# R111F.net
KiCad netlist of a schematic drawn in EAGLE
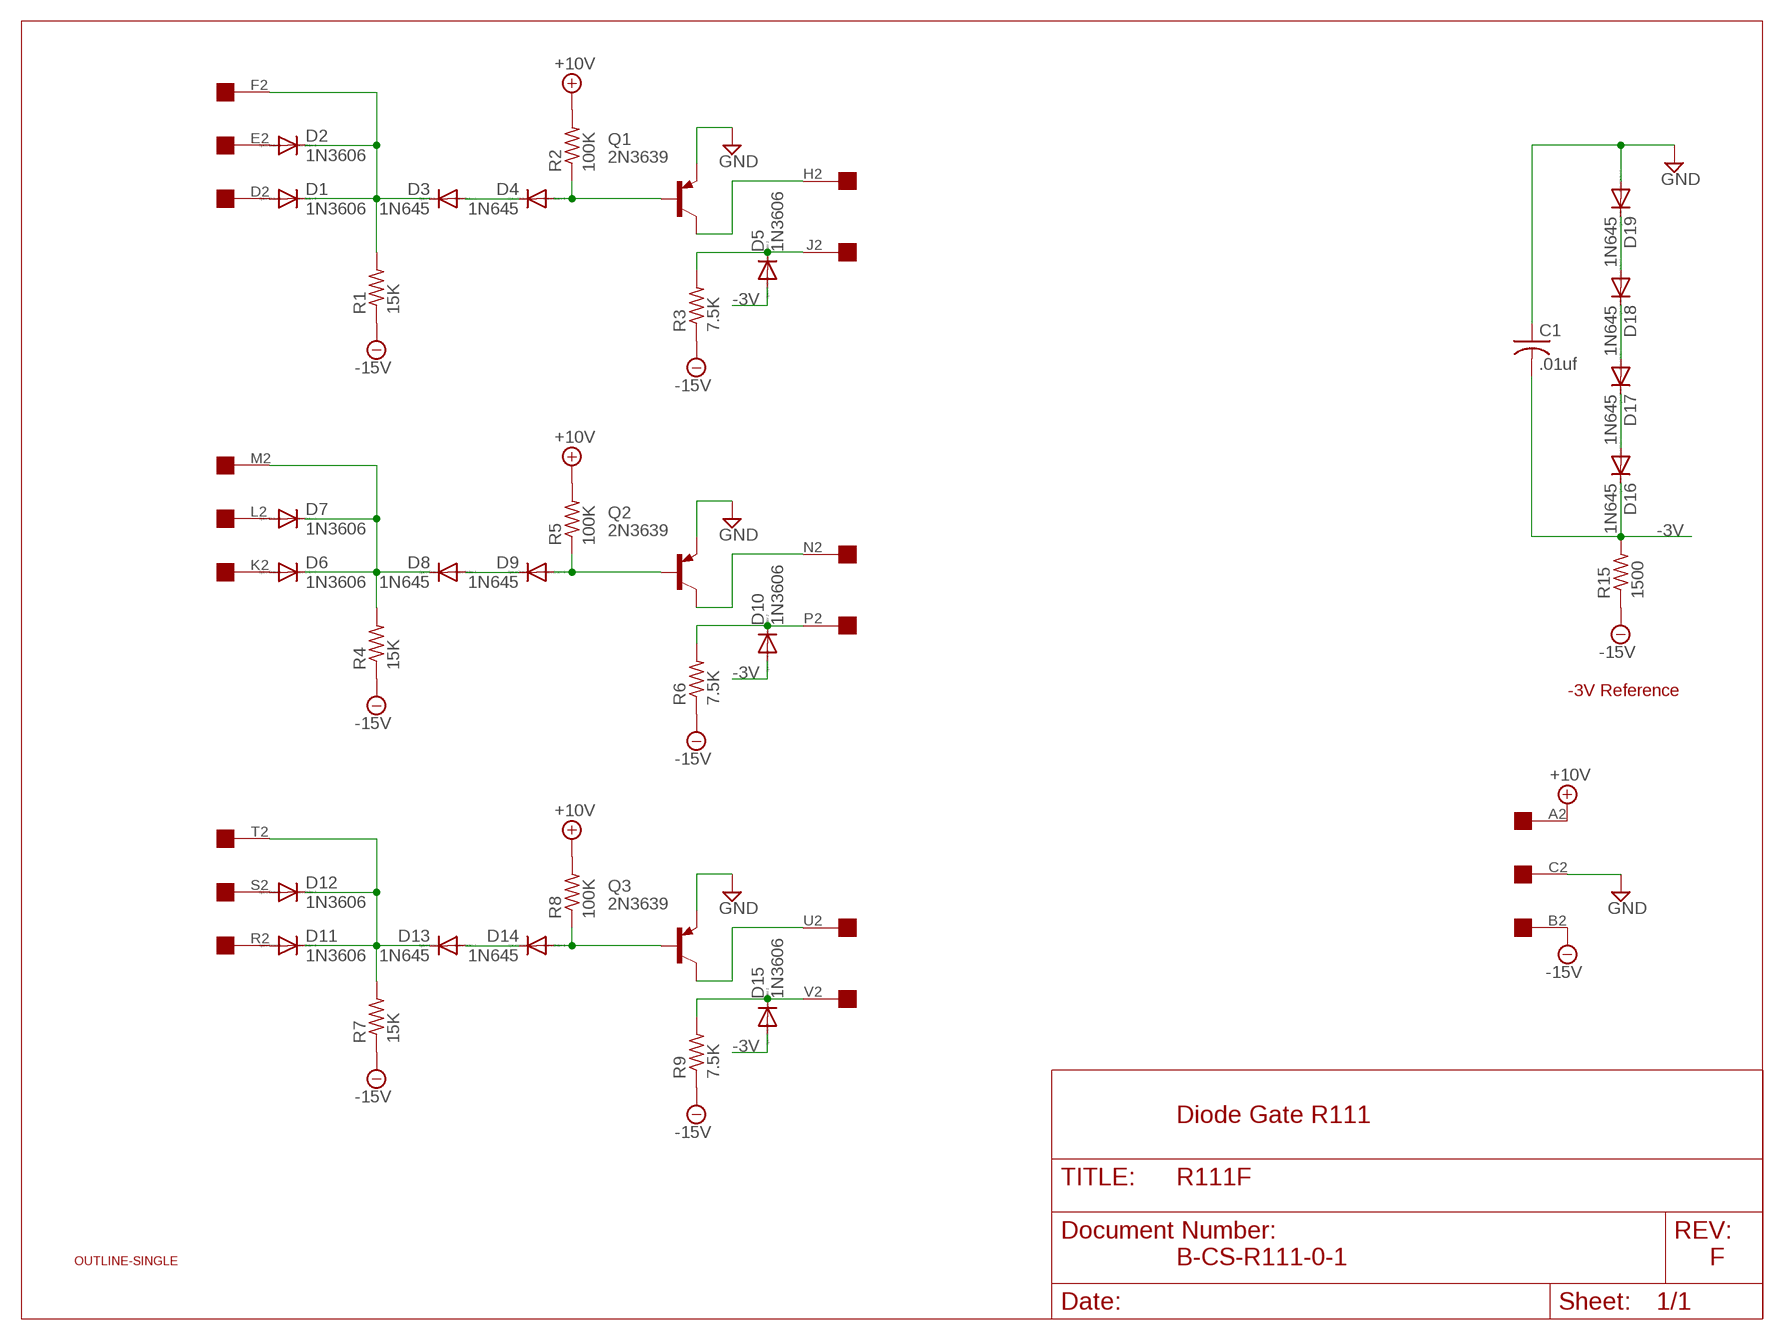
[diagram p0: schematic, sheet 1]

(export (version "E")
  (design (tool "Eeschema 10.0.6"))
  (components
    (comp (ref "C1")
      (value ".01uf")
      (footprint "eagle-import:C063-025X075")
      (libsource (lib "eagle-import") (part "C-US"))
    )
    (comp (ref "D1")
      (value "1N3606")
      (footprint "eagle-import:DO35-10")
      (libsource (lib "eagle-import") (part "1N4148DO35-10"))
    )
    (comp (ref "D2")
      (value "1N3606")
      (footprint "eagle-import:DO35-10")
      (libsource (lib "eagle-import") (part "1N4148DO35-10"))
    )
    (comp (ref "D3")
      (value "1N645")
      (footprint "eagle-import:DO35-10")
      (libsource (lib "eagle-import") (part "1N4148DO35-10"))
    )
    (comp (ref "D4")
      (value "1N645")
      (footprint "eagle-import:DO35-10")
      (libsource (lib "eagle-import") (part "1N4148DO35-10"))
    )
    (comp (ref "D5")
      (value "1N3606")
      (footprint "eagle-import:DO35-10")
      (libsource (lib "eagle-import") (part "1N4148DO35-10"))
    )
    (comp (ref "D6")
      (value "1N3606")
      (footprint "eagle-import:DO35-10")
      (libsource (lib "eagle-import") (part "1N4148DO35-10"))
    )
    (comp (ref "D7")
      (value "1N3606")
      (footprint "eagle-import:DO35-10")
      (libsource (lib "eagle-import") (part "1N4148DO35-10"))
    )
    (comp (ref "D8")
      (value "1N645")
      (footprint "eagle-import:DO35-10")
      (libsource (lib "eagle-import") (part "1N4148DO35-10"))
    )
    (comp (ref "D9")
      (value "1N645")
      (footprint "eagle-import:DO35-10")
      (libsource (lib "eagle-import") (part "1N4148DO35-10"))
    )
    (comp (ref "D10")
      (value "1N3606")
      (footprint "eagle-import:DO35-10")
      (libsource (lib "eagle-import") (part "1N4148DO35-10"))
    )
    (comp (ref "D11")
      (value "1N3606")
      (footprint "eagle-import:DO35-10")
      (libsource (lib "eagle-import") (part "1N4148DO35-10"))
    )
    (comp (ref "D12")
      (value "1N3606")
      (footprint "eagle-import:DO35-10")
      (libsource (lib "eagle-import") (part "1N4148DO35-10"))
    )
    (comp (ref "D13")
      (value "1N645")
      (footprint "eagle-import:DO35-10")
      (libsource (lib "eagle-import") (part "1N4148DO35-10"))
    )
    (comp (ref "D14")
      (value "1N645")
      (footprint "eagle-import:DO35-10")
      (libsource (lib "eagle-import") (part "1N4148DO35-10"))
    )
    (comp (ref "D15")
      (value "1N3606")
      (footprint "eagle-import:DO35-10")
      (libsource (lib "eagle-import") (part "1N4148DO35-10"))
    )
    (comp (ref "D16")
      (value "1N645")
      (footprint "eagle-import:DO35-10")
      (libsource (lib "eagle-import") (part "1N4148DO35-10"))
    )
    (comp (ref "D17")
      (value "1N645")
      (footprint "eagle-import:DO35-10")
      (libsource (lib "eagle-import") (part "1N4148DO35-10"))
    )
    (comp (ref "D18")
      (value "1N645")
      (footprint "eagle-import:DO35-10")
      (libsource (lib "eagle-import") (part "1N4148DO35-10"))
    )
    (comp (ref "D19")
      (value "1N645")
      (footprint "eagle-import:DO35-10")
      (libsource (lib "eagle-import") (part "1N4148DO35-10"))
    )
    (comp (ref "Q1")
      (value "2N3639")
      (footprint "eagle-import:TO39")
      (libsource (lib "eagle-import") (part "2N3637"))
    )
    (comp (ref "Q2")
      (value "2N3639")
      (footprint "eagle-import:TO39")
      (libsource (lib "eagle-import") (part "2N3637"))
    )
    (comp (ref "Q3")
      (value "2N3639")
      (footprint "eagle-import:TO39")
      (libsource (lib "eagle-import") (part "2N3637"))
    )
    (comp (ref "R1")
      (value "15K")
      (footprint "eagle-import:0207_10")
      (libsource (lib "eagle-import") (part "R-US_0207/10"))
    )
    (comp (ref "R2")
      (value "100K")
      (footprint "eagle-import:0207_10")
      (libsource (lib "eagle-import") (part "R-US_0207/10"))
    )
    (comp (ref "R3")
      (value "7.5K")
      (footprint "eagle-import:0207_10")
      (libsource (lib "eagle-import") (part "R-US_0207/10"))
    )
    (comp (ref "R4")
      (value "15K")
      (footprint "eagle-import:0207_10")
      (libsource (lib "eagle-import") (part "R-US_0207/10"))
    )
    (comp (ref "R5")
      (value "100K")
      (footprint "eagle-import:0207_10")
      (libsource (lib "eagle-import") (part "R-US_0207/10"))
    )
    (comp (ref "R6")
      (value "7.5K")
      (footprint "eagle-import:0207_10")
      (libsource (lib "eagle-import") (part "R-US_0207/10"))
    )
    (comp (ref "R7")
      (value "15K")
      (footprint "eagle-import:0207_10")
      (libsource (lib "eagle-import") (part "R-US_0207/10"))
    )
    (comp (ref "R8")
      (value "100K")
      (footprint "eagle-import:0207_10")
      (libsource (lib "eagle-import") (part "R-US_0207/10"))
    )
    (comp (ref "R9")
      (value "7.5K")
      (footprint "eagle-import:0207_10")
      (libsource (lib "eagle-import") (part "R-US_0207/10"))
    )
    (comp (ref "R15")
      (value "1500")
      (footprint "eagle-import:0207_10")
      (libsource (lib "eagle-import") (part "R-US_0207/10"))
    )
    (comp (ref "U$1")
      (value "OUTLINE-SINGLE")
      (footprint "eagle-import:SINGLE")
      (libsource (lib "eagle-import") (part "OUTLINE-SINGLE"))
    )
    (comp (ref "U$2")
      (value "EDGE-1")
      (footprint "eagle-import:EDGE-CON1")
      (libsource (lib "eagle-import") (part "EDGE-1"))
    )
  )
  (nets
    (net (code "1") (name "+10V") (class "Default")
      (node (ref "R2") (pin "2") (pinfunction "2_2") (pintype "passive"))
      (node (ref "R5") (pin "2") (pinfunction "2_2") (pintype "passive"))
      (node (ref "R8") (pin "2") (pinfunction "2_2") (pintype "passive"))
      (node (ref "U$2") (pin "A2") (pinfunction "1_A2") (pintype "bidirectional"))
    )
    (net (code "2") (name "-15V") (class "Default")
      (node (ref "R1") (pin "1") (pinfunction "1_1") (pintype "passive"))
      (node (ref "R15") (pin "1") (pinfunction "1_1") (pintype "passive"))
      (node (ref "R3") (pin "1") (pinfunction "1_1") (pintype "passive"))
      (node (ref "R4") (pin "1") (pinfunction "1_1") (pintype "passive"))
      (node (ref "R6") (pin "1") (pinfunction "1_1") (pintype "passive"))
      (node (ref "R7") (pin "1") (pinfunction "1_1") (pintype "passive"))
      (node (ref "R9") (pin "1") (pinfunction "1_1") (pintype "passive"))
      (node (ref "U$2") (pin "B2") (pinfunction "1_B2") (pintype "bidirectional"))
    )
    (net (code "3") (name "/-3V") (class "Default")
      (node (ref "C1") (pin "2") (pinfunction "2_2") (pintype "passive"))
      (node (ref "D10") (pin "A") (pinfunction "A_A") (pintype "passive"))
      (node (ref "D15") (pin "A") (pinfunction "A_A") (pintype "passive"))
      (node (ref "D16") (pin "C") (pinfunction "C_C") (pintype "passive"))
      (node (ref "D5") (pin "A") (pinfunction "A_A") (pintype "passive"))
      (node (ref "R15") (pin "2") (pinfunction "2_2") (pintype "passive"))
    )
    (net (code "4") (name "GND") (class "Default")
      (node (ref "C1") (pin "1") (pinfunction "1_1") (pintype "passive"))
      (node (ref "D19") (pin "A") (pinfunction "A_A") (pintype "passive"))
      (node (ref "Q1") (pin "1") (pinfunction "E_1") (pintype "passive"))
      (node (ref "Q2") (pin "1") (pinfunction "E_1") (pintype "passive"))
      (node (ref "Q3") (pin "1") (pinfunction "E_1") (pintype "passive"))
      (node (ref "U$2") (pin "C2") (pinfunction "1_C2") (pintype "bidirectional"))
    )
    (net (code "5") (name "Net-(D3-PadA)") (class "Default")
      (node (ref "D3") (pin "A") (pinfunction "A_A") (pintype "passive"))
      (node (ref "D4") (pin "C") (pinfunction "C_C") (pintype "passive"))
    )
    (net (code "6") (name "Net-(D8-PadA)") (class "Default")
      (node (ref "D8") (pin "A") (pinfunction "A_A") (pintype "passive"))
      (node (ref "D9") (pin "C") (pinfunction "C_C") (pintype "passive"))
    )
    (net (code "7") (name "Net-(D13-PadA)") (class "Default")
      (node (ref "D13") (pin "A") (pinfunction "A_A") (pintype "passive"))
      (node (ref "D14") (pin "C") (pinfunction "C_C") (pintype "passive"))
    )
    (net (code "8") (name "Net-(D16-PadA)") (class "Default")
      (node (ref "D16") (pin "A") (pinfunction "A_A") (pintype "passive"))
      (node (ref "D17") (pin "C") (pinfunction "C_C") (pintype "passive"))
    )
    (net (code "9") (name "Net-(D17-PadA)") (class "Default")
      (node (ref "D17") (pin "A") (pinfunction "A_A") (pintype "passive"))
      (node (ref "D18") (pin "C") (pinfunction "C_C") (pintype "passive"))
    )
    (net (code "10") (name "Net-(D18-PadA)") (class "Default")
      (node (ref "D18") (pin "A") (pinfunction "A_A") (pintype "passive"))
      (node (ref "D19") (pin "C") (pinfunction "C_C") (pintype "passive"))
    )
    (net (code "11") (name "Net-(Q1-B)") (class "Default")
      (node (ref "D4") (pin "A") (pinfunction "A_A") (pintype "passive"))
      (node (ref "Q1") (pin "2") (pinfunction "B_2") (pintype "passive"))
      (node (ref "R2") (pin "1") (pinfunction "1_1") (pintype "passive"))
    )
    (net (code "12") (name "Net-(Q1-C)") (class "Default")
      (node (ref "Q1") (pin "3") (pinfunction "C_3") (pintype "passive"))
      (node (ref "U$2") (pin "H2") (pinfunction "1_H2") (pintype "bidirectional"))
    )
    (net (code "13") (name "Net-(Q2-B)") (class "Default")
      (node (ref "D9") (pin "A") (pinfunction "A_A") (pintype "passive"))
      (node (ref "Q2") (pin "2") (pinfunction "B_2") (pintype "passive"))
      (node (ref "R5") (pin "1") (pinfunction "1_1") (pintype "passive"))
    )
    (net (code "14") (name "Net-(Q2-C)") (class "Default")
      (node (ref "Q2") (pin "3") (pinfunction "C_3") (pintype "passive"))
      (node (ref "U$2") (pin "N2") (pinfunction "1_N2") (pintype "bidirectional"))
    )
    (net (code "15") (name "Net-(Q3-B)") (class "Default")
      (node (ref "D14") (pin "A") (pinfunction "A_A") (pintype "passive"))
      (node (ref "Q3") (pin "2") (pinfunction "B_2") (pintype "passive"))
      (node (ref "R8") (pin "1") (pinfunction "1_1") (pintype "passive"))
    )
    (net (code "16") (name "Net-(Q3-C)") (class "Default")
      (node (ref "Q3") (pin "3") (pinfunction "C_3") (pintype "passive"))
      (node (ref "U$2") (pin "U2") (pinfunction "1_U2") (pintype "bidirectional"))
    )
    (net (code "17") (name "Net-(U$2D-1)") (class "Default")
      (node (ref "D1") (pin "A") (pinfunction "A_A") (pintype "passive"))
      (node (ref "U$2") (pin "D2") (pinfunction "1_D2") (pintype "bidirectional"))
    )
    (net (code "18") (name "Net-(U$2E-1)") (class "Default")
      (node (ref "D2") (pin "A") (pinfunction "A_A") (pintype "passive"))
      (node (ref "U$2") (pin "E2") (pinfunction "1_E2") (pintype "bidirectional"))
    )
    (net (code "19") (name "Net-(U$2F-1)") (class "Default")
      (node (ref "D1") (pin "C") (pinfunction "C_C") (pintype "passive"))
      (node (ref "D2") (pin "C") (pinfunction "C_C") (pintype "passive"))
      (node (ref "D3") (pin "C") (pinfunction "C_C") (pintype "passive"))
      (node (ref "R1") (pin "2") (pinfunction "2_2") (pintype "passive"))
      (node (ref "U$2") (pin "F2") (pinfunction "1_F2") (pintype "bidirectional"))
    )
    (net (code "20") (name "Net-(U$2H-1)") (class "Default")
      (node (ref "D5") (pin "C") (pinfunction "C_C") (pintype "passive"))
      (node (ref "R3") (pin "2") (pinfunction "2_2") (pintype "passive"))
      (node (ref "U$2") (pin "J2") (pinfunction "1_J2") (pintype "bidirectional"))
    )
    (net (code "21") (name "Net-(U$2I-1)") (class "Default")
      (node (ref "D6") (pin "A") (pinfunction "A_A") (pintype "passive"))
      (node (ref "U$2") (pin "K2") (pinfunction "1_K2") (pintype "bidirectional"))
    )
    (net (code "22") (name "Net-(U$2J-1)") (class "Default")
      (node (ref "D7") (pin "A") (pinfunction "A_A") (pintype "passive"))
      (node (ref "U$2") (pin "L2") (pinfunction "1_L2") (pintype "bidirectional"))
    )
    (net (code "23") (name "Net-(U$2K-1)") (class "Default")
      (node (ref "D6") (pin "C") (pinfunction "C_C") (pintype "passive"))
      (node (ref "D7") (pin "C") (pinfunction "C_C") (pintype "passive"))
      (node (ref "D8") (pin "C") (pinfunction "C_C") (pintype "passive"))
      (node (ref "R4") (pin "2") (pinfunction "2_2") (pintype "passive"))
      (node (ref "U$2") (pin "M2") (pinfunction "1_M2") (pintype "bidirectional"))
    )
    (net (code "24") (name "Net-(U$2M-1)") (class "Default")
      (node (ref "D10") (pin "C") (pinfunction "C_C") (pintype "passive"))
      (node (ref "R6") (pin "2") (pinfunction "2_2") (pintype "passive"))
      (node (ref "U$2") (pin "P2") (pinfunction "1_P2") (pintype "bidirectional"))
    )
    (net (code "25") (name "Net-(U$2N-1)") (class "Default")
      (node (ref "D11") (pin "A") (pinfunction "A_A") (pintype "passive"))
      (node (ref "U$2") (pin "R2") (pinfunction "1_R2") (pintype "bidirectional"))
    )
    (net (code "26") (name "Net-(U$2O-1)") (class "Default")
      (node (ref "D12") (pin "A") (pinfunction "A_A") (pintype "passive"))
      (node (ref "U$2") (pin "S2") (pinfunction "1_S2") (pintype "bidirectional"))
    )
    (net (code "27") (name "Net-(U$2P-1)") (class "Default")
      (node (ref "D11") (pin "C") (pinfunction "C_C") (pintype "passive"))
      (node (ref "D12") (pin "C") (pinfunction "C_C") (pintype "passive"))
      (node (ref "D13") (pin "C") (pinfunction "C_C") (pintype "passive"))
      (node (ref "R7") (pin "2") (pinfunction "2_2") (pintype "passive"))
      (node (ref "U$2") (pin "T2") (pinfunction "1_T2") (pintype "bidirectional"))
    )
    (net (code "28") (name "Net-(U$2R-1)") (class "Default")
      (node (ref "D15") (pin "C") (pinfunction "C_C") (pintype "passive"))
      (node (ref "R9") (pin "2") (pinfunction "2_2") (pintype "passive"))
      (node (ref "U$2") (pin "V2") (pinfunction "1_V2") (pintype "bidirectional"))
    )
  )
)
